# 04_TYPEC.net
KiCad netlist of a schematic drawn in Altium Designer
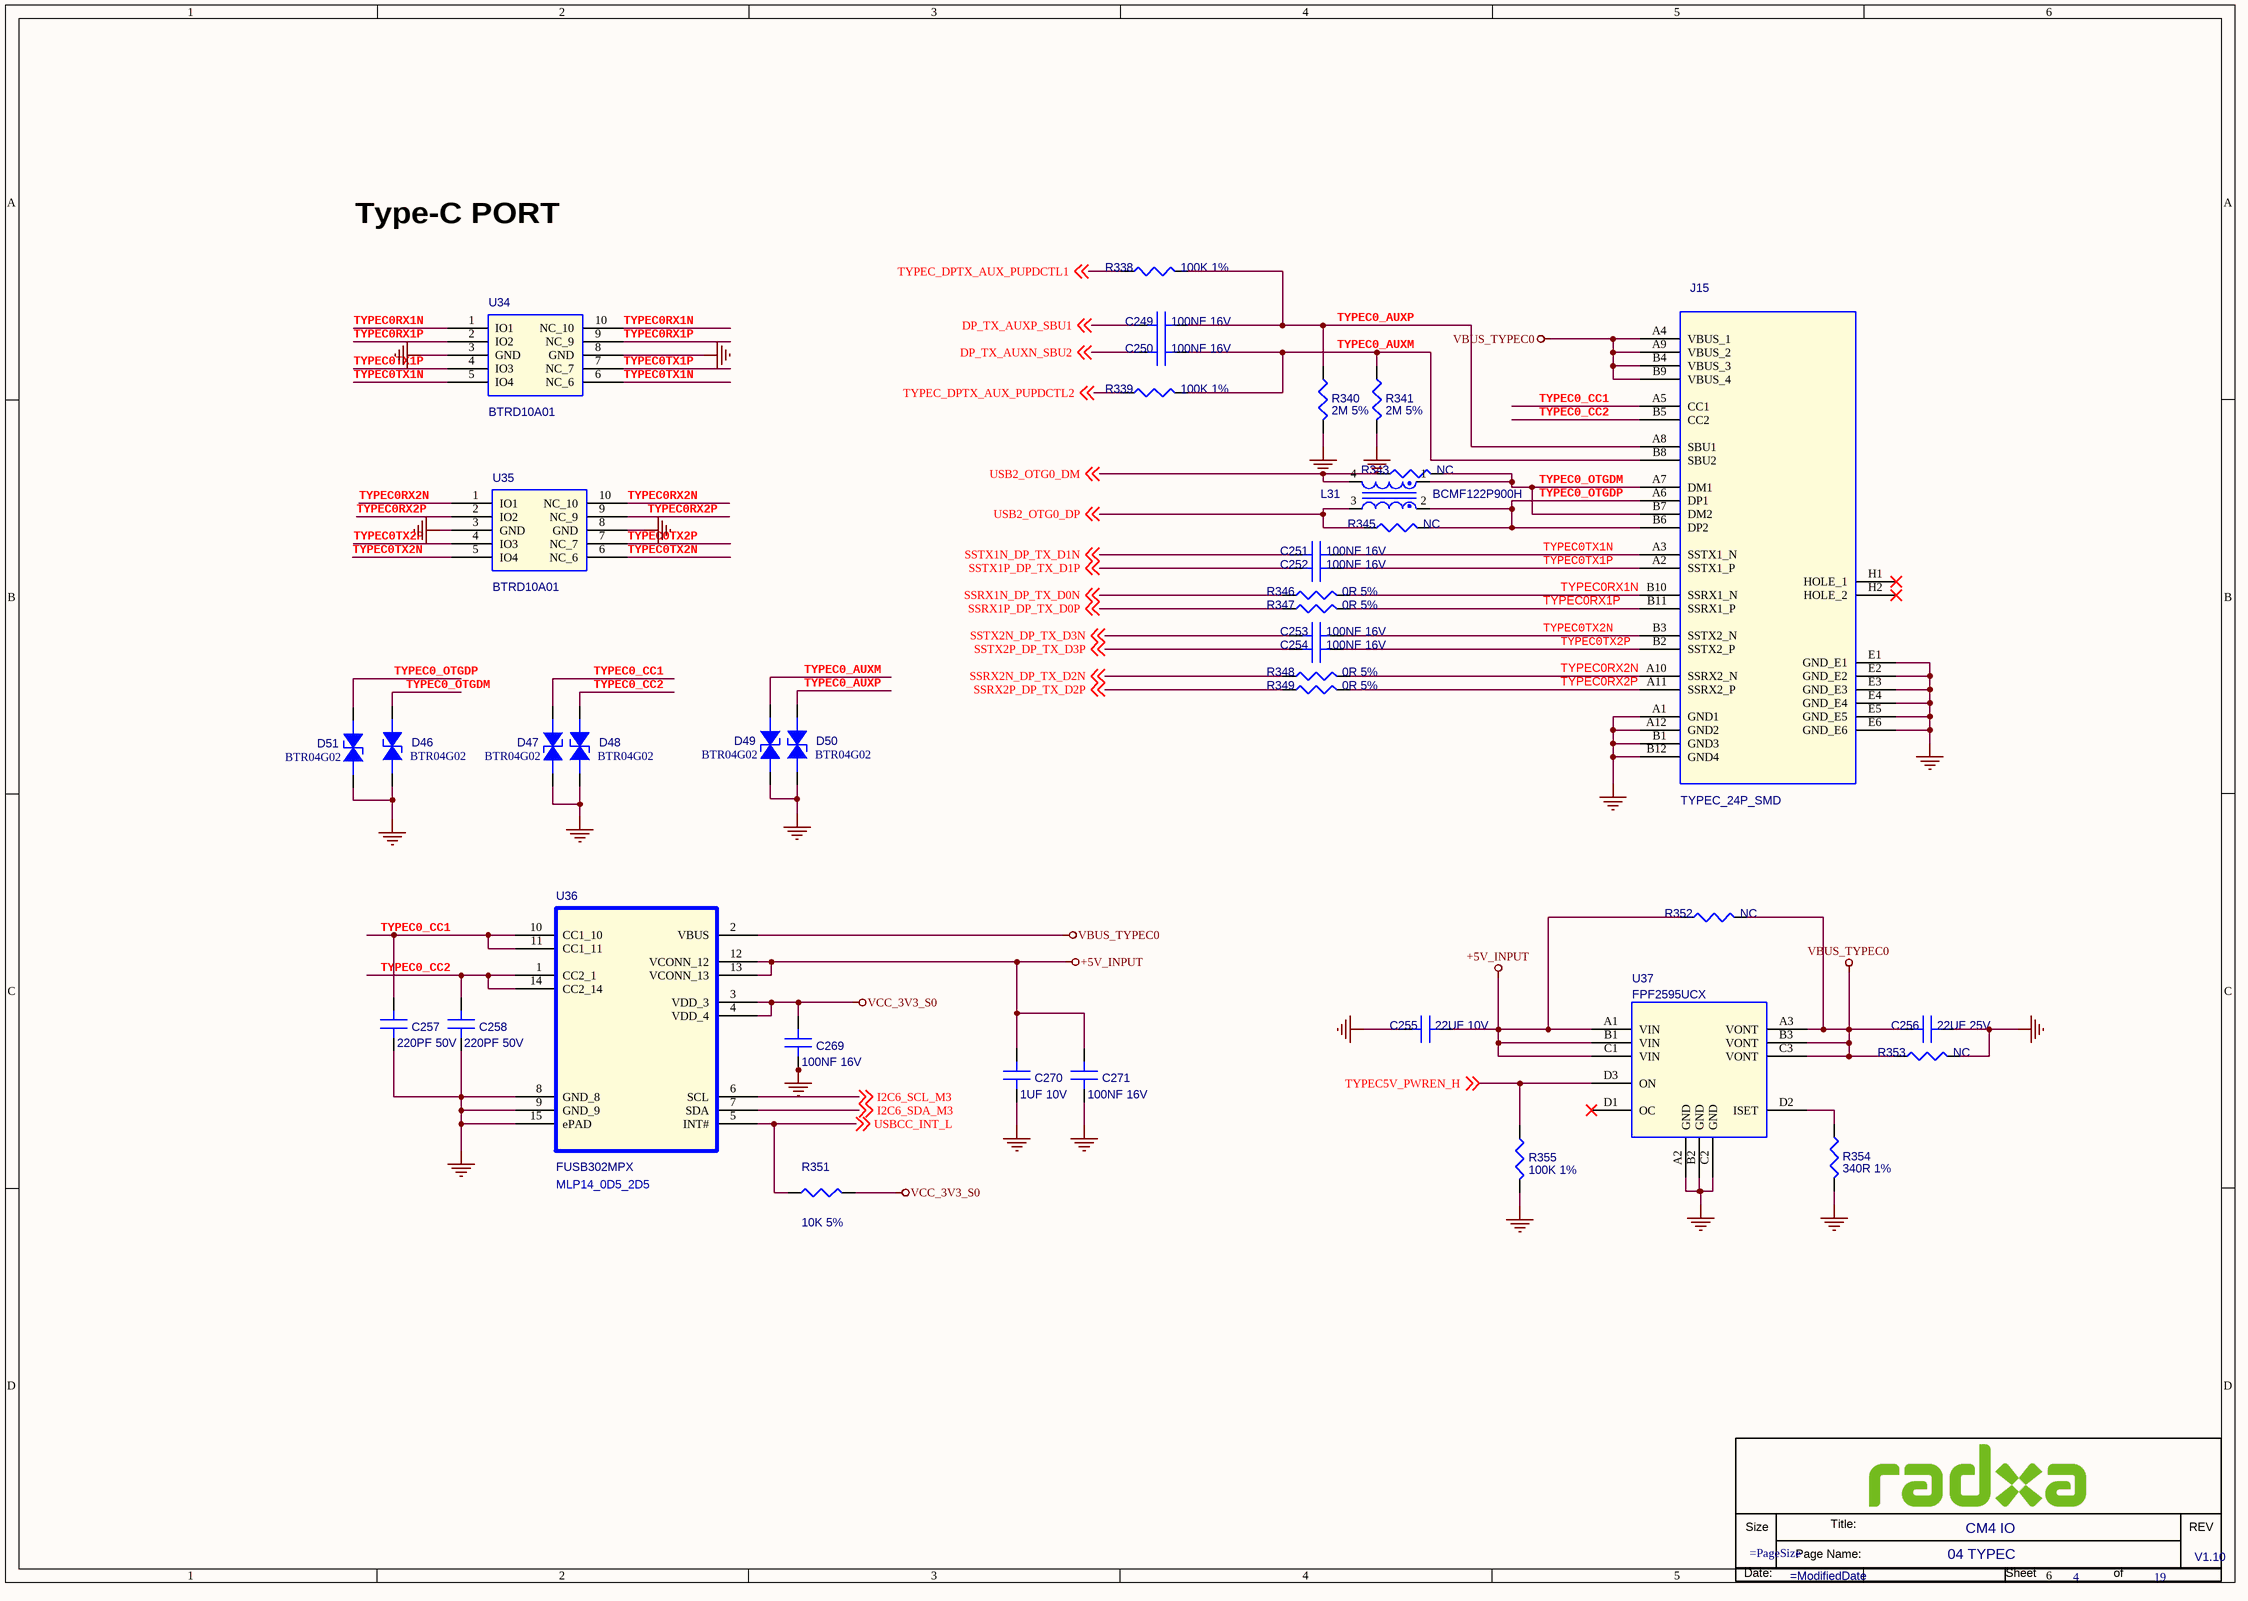
[diagram p0: 04 TYPEC.SchDoc]

(export (version "E")
  (design (tool "Eeschema 10.0.6"))
  (components
    (comp (ref "C249")
      (value "100NF 16V")
      (footprint "C0201")
      (description "SMD  0201  100NF  16V  X5R  ±20%  ROHS")
      (fields (field (name "PART NUMBER") "A1C01.00099"))
      (libsource (lib "*") (part "C"))
    )
    (comp (ref "C250")
      (value "100NF 16V")
      (footprint "C0201")
      (description "SMD  0201  100NF  16V  X5R  ±20%  ROHS")
      (fields (field (name "PART NUMBER") "A1C01.00099"))
      (libsource (lib "*") (part "C"))
    )
    (comp (ref "C251")
      (value "100NF 16V")
      (footprint "C0201")
      (description "SMD  0201  100NF  16V  X5R  ±20%  ROHS")
      (fields (field (name "PART NUMBER") "A1C01.00099"))
      (libsource (lib "*") (part "C"))
    )
    (comp (ref "C252")
      (value "100NF 16V")
      (footprint "C0201")
      (description "SMD  0201  100NF  16V  X5R  ±20%  ROHS")
      (fields (field (name "PART NUMBER") "A1C01.00099"))
      (libsource (lib "*") (part "C"))
    )
    (comp (ref "C253")
      (value "100NF 16V")
      (footprint "C0201")
      (description "SMD  0201  100NF  16V  X5R  ±20%  ROHS")
      (fields (field (name "PART NUMBER") "A1C01.00099"))
      (libsource (lib "*") (part "C"))
    )
    (comp (ref "C254")
      (value "100NF 16V")
      (footprint "C0201")
      (description "SMD  0201  100NF  16V  X5R  ±20%  ROHS")
      (fields (field (name "PART NUMBER") "A1C01.00099"))
      (libsource (lib "*") (part "C"))
    )
    (comp (ref "C255")
      (value "22UF 10V")
      (footprint "C0603")
      (description "SMD  0603  22UF  10V  X5R  ±20%  ROHS")
      (fields (field (name "PART NUMBER") "A1C01.00015"))
      (libsource (lib "*") (part "C"))
    )
    (comp (ref "C256")
      (value "22UF 25V")
      (footprint "C0805")
      (description "SMD  0805  22UF  25V  X5R  ±20%  ROHS")
      (fields (field (name "PART NUMBER") "A1C01.00249"))
      (libsource (lib "*") (part "C"))
    )
    (comp (ref "C257")
      (value "220PF 50V")
      (footprint "C0201")
      (description "SMD  0201  220PF  50V  NPO  ±5%  ROHS")
      (fields (field (name "PART NUMBER") "A1C01.00383"))
      (libsource (lib "*") (part "C"))
    )
    (comp (ref "C258")
      (value "220PF 50V")
      (footprint "C0201")
      (description "SMD  0201  220PF  50V  NPO  ±5%  ROHS")
      (fields (field (name "PART NUMBER") "A1C01.00383"))
      (libsource (lib "*") (part "C"))
    )
    (comp (ref "C269")
      (value "100NF 16V")
      (footprint "C0201")
      (description "SMD  0201  100NF  16V  X5R  ±20%  ROHS")
      (fields (field (name "PART NUMBER") "A1C01.00099"))
      (libsource (lib "*") (part "C"))
    )
    (comp (ref "C270")
      (value "1UF 10V")
      (footprint "C0201")
      (description "SMD  0201  1UF  10V  X5R  ±20%  ROHS")
      (fields (field (name "PART NUMBER") "A1C01.00081"))
      (libsource (lib "*") (part "C"))
    )
    (comp (ref "C271")
      (value "100NF 16V")
      (footprint "C0201")
      (description "SMD  0201  100NF  16V  X5R  ±20%  ROHS")
      (fields (field (name "PART NUMBER") "A1C01.00099"))
      (libsource (lib "*") (part "C"))
    )
    (comp (ref "D46")
      (value "BTR04G02")
      (footprint "DFN1006-2L")
      (description "SMD  编带  0402  BTR04G02  B-tron  ROHS")
      (fields (field (name "PART NUMBER") "A1D02.00002"))
      (libsource (lib "*") (part "ESD"))
    )
    (comp (ref "D47")
      (value "BTR04G02")
      (footprint "DFN1006-2L")
      (description "SMD  编带  0402  BTR04G02  B-tron  ROHS")
      (fields (field (name "PART NUMBER") "A1D02.00002"))
      (libsource (lib "*") (part "ESD"))
    )
    (comp (ref "D48")
      (value "BTR04G02")
      (footprint "DFN1006-2L")
      (description "SMD  编带  0402  BTR04G02  B-tron  ROHS")
      (fields (field (name "PART NUMBER") "A1D02.00002"))
      (libsource (lib "*") (part "ESD"))
    )
    (comp (ref "D49")
      (value "BTR04G02")
      (footprint "DFN1006-2L")
      (description "SMD  编带  0402  BTR04G02  B-tron  ROHS")
      (fields (field (name "PART NUMBER") "A1D02.00002"))
      (libsource (lib "*") (part "ESD"))
    )
    (comp (ref "D50")
      (value "BTR04G02")
      (footprint "DFN1006-2L")
      (description "SMD  编带  0402  BTR04G02  B-tron  ROHS")
      (fields (field (name "PART NUMBER") "A1D02.00002"))
      (libsource (lib "*") (part "ESD"))
    )
    (comp (ref "D51")
      (value "BTR04G02")
      (footprint "DFN1006-2L")
      (description "SMD  编带  0402  BTR04G02  B-tron  ROHS")
      (fields (field (name "PART NUMBER") "A1D02.00002"))
      (libsource (lib "*") (part "ESD"))
    )
    (comp (ref "J15")
      (value "TYPEC_24P_SMD")
      (footprint "TYPEC_SM24P_0D5")
      (description "SMD  母座  2*12PIN  双排  8.94x7.9xH3.2mm  带定位柱  不锈钢  兴联  BUSF242B3N11677  ROHS")
      (fields (field (name "PART NUMBER") "A1J04.00021"))
      (libsource (lib "*") (part "TYPEC_24P_SMD_2"))
    )
    (comp (ref "L31")
      (value "BCMF122P900H")
      (footprint "LC1210")
      (description "SMD  BCMF122P900H  90R  4PIN  不带ESD  ±5%  B-tron  ROHS")
      (fields (field (name "PART NUMBER") "A1L03.00003"))
      (libsource (lib "*") (part "MCZ1210AH900L2"))
    )
    (comp (ref "R338")
      (value "100K 1%")
      (footprint "R0402")
      (description "SMD  0201  100K  1/20W  ±1%  ROHS")
      (fields (field (name "PART NUMBER") "A1R01.00165"))
      (libsource (lib "*") (part "R"))
    )
    (comp (ref "R339")
      (value "100K 1%")
      (footprint "R0402")
      (description "SMD  0201  100K  1/20W  ±1%  ROHS")
      (fields (field (name "PART NUMBER") "A1R01.00165"))
      (libsource (lib "*") (part "R"))
    )
    (comp (ref "R340")
      (value "2M 5%")
      (footprint "R0402")
      (description "SMD  0201  2M  1/20W  ±5%  ROHS")
      (fields (field (name "PART NUMBER") "A1R01.00114"))
      (libsource (lib "*") (part "R"))
    )
    (comp (ref "R341")
      (value "2M 5%")
      (footprint "R0402")
      (description "SMD  0201  2M  1/20W  ±5%  ROHS")
      (fields (field (name "PART NUMBER") "A1R01.00114"))
      (libsource (lib "*") (part "R"))
    )
    (comp (ref "R343")
      (value "NC")
      (footprint "R0402")
      (description "SMD  0201  0R  1/20W  ±5%  ROHS")
      (fields (field (name "PART NUMBER") "A1R01.00027"))
      (libsource (lib "*") (part "R"))
    )
    (comp (ref "R345")
      (value "NC")
      (footprint "R0402")
      (description "SMD  0201  0R  1/20W  ±5%  ROHS")
      (fields (field (name "PART NUMBER") "A1R01.00027"))
      (libsource (lib "*") (part "R"))
    )
    (comp (ref "R346")
      (value "0R 5%")
      (footprint "R0402")
      (description "SMD  0201  0R  1/20W  ±5%  ROHS")
      (fields (field (name "PART NUMBER") "A1R01.00027"))
      (libsource (lib "*") (part "R"))
    )
    (comp (ref "R347")
      (value "0R 5%")
      (footprint "R0402")
      (description "SMD  0201  0R  1/20W  ±5%  ROHS")
      (fields (field (name "PART NUMBER") "A1R01.00027"))
      (libsource (lib "*") (part "R"))
    )
    (comp (ref "R348")
      (value "0R 5%")
      (footprint "R0402")
      (description "SMD  0201  0R  1/20W  ±5%  ROHS")
      (fields (field (name "PART NUMBER") "A1R01.00027"))
      (libsource (lib "*") (part "R"))
    )
    (comp (ref "R349")
      (value "0R 5%")
      (footprint "R0402")
      (description "SMD  0201  0R  1/20W  ±5%  ROHS")
      (fields (field (name "PART NUMBER") "A1R01.00027"))
      (libsource (lib "*") (part "R"))
    )
    (comp (ref "R351")
      (value "10K 5%")
      (footprint "R0402")
      (description "SMD  0201  10K  1/20W  ±5%  ROHS")
      (fields (field (name "PART NUMBER") "A1R01.00012"))
      (libsource (lib "*") (part "R"))
    )
    (comp (ref "R352")
      (value "NC")
      (footprint "R0402")
      (description "SMD  0402  0R  1/16W  ±5%  ROHS")
      (fields (field (name "PART NUMBER") "A1R01.00030"))
      (libsource (lib "*") (part "R"))
    )
    (comp (ref "R353")
      (value "NC")
      (footprint "R0402")
      (description "SMD  0201  4.7K  1/20W  ±5%  ROHS")
      (fields (field (name "PART NUMBER") "A1R01.00014"))
      (libsource (lib "*") (part "R"))
    )
    (comp (ref "R354")
      (value "340R 1%")
      (footprint "R0402")
      (description "SMD  0201  340R  1/20W  ±1%  ROHS")
      (fields (field (name "PART NUMBER") "A1R01.00512"))
      (libsource (lib "*") (part "R"))
    )
    (comp (ref "R355")
      (value "100K 1%")
      (footprint "R0402")
      (description "SMD  0201  100K  1/20W  ±1%  ROHS")
      (fields (field (name "PART NUMBER") "A1R01.00165"))
      (libsource (lib "*") (part "R"))
    )
    (comp (ref "U34")
      (value "BTRD10A01")
      (footprint "SON10_0D5_1")
      (description "SMD  编带  DFN2510-10L  BTRD10A01  4Line  0.1pF  B-tron  ROHS")
      (fields (field (name "PART NUMBER") "A1D02.00106"))
      (libsource (lib "*") (part "BTRD10A01"))
    )
    (comp (ref "U35")
      (value "BTRD10A01")
      (footprint "SON10_0D5_1")
      (description "SMD  编带  DFN2510-10L  BTRD10A01  4Line  0.1pF  B-tron  ROHS")
      (fields (field (name "PART NUMBER") "A1D02.00106"))
      (libsource (lib "*") (part "BTRD10A01"))
    )
    (comp (ref "U36")
      (value "FUSB302MPX")
      (footprint "MLP14_0D5_2D5")
      (description "SMD  USB转换芯片  FUSB302MPX  MLP14  onsemi(安森美)  ROHS")
      (fields (field (name "PCB FOOTPRINT") "MLP14_0D5_2D5") (field (name "PART NUMBER") "A1I01.00760"))
      (libsource (lib "*") (part "FUSB302MPX"))
    )
    (comp (ref "U37")
      (value "FPF2595UCX")
      (footprint "WLCSP12_0D4_1D5")
      (description "SMD  功率电子开关  FPF2595UCX  WLCSP12  ON(安森美)  ROHS")
      (fields (field (name "PART NUMBER") "A1I01.00675"))
      (libsource (lib "*") (part "FPF2595UCX"))
    )
  )
  (nets
    (net (code "1") (name "+5V_INPUT") (class "Default")
      (node (ref "C255") (pin "1") (pinfunction "A_1") (pintype "passive"))
      (node (ref "C270") (pin "1") (pinfunction "A_1") (pintype "passive"))
      (node (ref "C271") (pin "1") (pinfunction "A_1") (pintype "passive"))
      (node (ref "R352") (pin "1") (pinfunction "1_1") (pintype "passive"))
      (node (ref "U36") (pin "12") (pinfunction "VCONN_12_12") (pintype "passive"))
      (node (ref "U36") (pin "13") (pinfunction "VCONN_13_13") (pintype "passive"))
      (node (ref "U37") (pin "A1") (pinfunction "VIN_A1") (pintype "power_in"))
      (node (ref "U37") (pin "B1") (pinfunction "VIN_B1") (pintype "power_in"))
      (node (ref "U37") (pin "C1") (pinfunction "VIN_C1") (pintype "power_in"))
    )
    (net (code "2") (name "/TYPEC0RX1N") (class "Default")
      (node (ref "J15") (pin "B10") (pinfunction "SSRX1_N_B10") (pintype "passive"))
      (node (ref "R346") (pin "2") (pinfunction "2_2") (pintype "passive"))
      (node (ref "U34") (pin "1") (pinfunction "IO1_1") (pintype "passive"))
      (node (ref "U34") (pin "10") (pinfunction "NC_10_10") (pintype "passive"))
    )
    (net (code "3") (name "/TYPEC0RX1P") (class "Default")
      (node (ref "J15") (pin "B11") (pinfunction "SSRX1_P_B11") (pintype "passive"))
      (node (ref "R347") (pin "2") (pinfunction "2_2") (pintype "passive"))
      (node (ref "U34") (pin "2") (pinfunction "IO2_2") (pintype "passive"))
      (node (ref "U34") (pin "9") (pinfunction "NC_9_9") (pintype "passive"))
    )
    (net (code "4") (name "/TYPEC0RX2N") (class "Default")
      (node (ref "J15") (pin "A10") (pinfunction "SSRX2_N_A10") (pintype "passive"))
      (node (ref "R348") (pin "2") (pinfunction "2_2") (pintype "passive"))
      (node (ref "U35") (pin "1") (pinfunction "IO1_1") (pintype "passive"))
      (node (ref "U35") (pin "10") (pinfunction "NC_10_10") (pintype "passive"))
    )
    (net (code "5") (name "/TYPEC0RX2P") (class "Default")
      (node (ref "J15") (pin "A11") (pinfunction "SSRX2_P_A11") (pintype "passive"))
      (node (ref "R349") (pin "2") (pinfunction "2_2") (pintype "passive"))
      (node (ref "U35") (pin "2") (pinfunction "IO2_2") (pintype "passive"))
      (node (ref "U35") (pin "9") (pinfunction "NC_9_9") (pintype "passive"))
    )
    (net (code "6") (name "/TYPEC0TX1N") (class "Default")
      (node (ref "C251") (pin "2") (pinfunction "B_2") (pintype "passive"))
      (node (ref "J15") (pin "A3") (pinfunction "SSTX1_N_A3") (pintype "passive"))
      (node (ref "U34") (pin "5") (pinfunction "IO4_5") (pintype "passive"))
      (node (ref "U34") (pin "6") (pinfunction "NC_6_6") (pintype "passive"))
    )
    (net (code "7") (name "/TYPEC0TX1P") (class "Default")
      (node (ref "C252") (pin "2") (pinfunction "B_2") (pintype "passive"))
      (node (ref "J15") (pin "A2") (pinfunction "SSTX1_P_A2") (pintype "passive"))
      (node (ref "U34") (pin "4") (pinfunction "IO3_4") (pintype "passive"))
      (node (ref "U34") (pin "7") (pinfunction "NC_7_7") (pintype "passive"))
    )
    (net (code "8") (name "/TYPEC0TX2N") (class "Default")
      (node (ref "C253") (pin "2") (pinfunction "B_2") (pintype "passive"))
      (node (ref "J15") (pin "B3") (pinfunction "SSTX2_N_B3") (pintype "passive"))
      (node (ref "U35") (pin "5") (pinfunction "IO4_5") (pintype "passive"))
      (node (ref "U35") (pin "6") (pinfunction "NC_6_6") (pintype "passive"))
    )
    (net (code "9") (name "/TYPEC0TX2P") (class "Default")
      (node (ref "C254") (pin "2") (pinfunction "B_2") (pintype "passive"))
      (node (ref "J15") (pin "B2") (pinfunction "SSTX2_P_B2") (pintype "passive"))
      (node (ref "U35") (pin "4") (pinfunction "IO3_4") (pintype "passive"))
      (node (ref "U35") (pin "7") (pinfunction "NC_7_7") (pintype "passive"))
    )
    (net (code "10") (name "/TYPEC0_AUXM") (class "Default")
      (node (ref "C250") (pin "2") (pinfunction "B_2") (pintype "passive"))
      (node (ref "D49") (pin "2") (pinfunction "CATHODE_2") (pintype "passive"))
      (node (ref "J15") (pin "B8") (pinfunction "SBU2_B8") (pintype "passive"))
      (node (ref "R339") (pin "2") (pinfunction "2_2") (pintype "passive"))
      (node (ref "R341") (pin "1") (pinfunction "1_1") (pintype "passive"))
    )
    (net (code "11") (name "/TYPEC0_AUXP") (class "Default")
      (node (ref "C249") (pin "2") (pinfunction "B_2") (pintype "passive"))
      (node (ref "D50") (pin "2") (pinfunction "CATHODE_2") (pintype "passive"))
      (node (ref "J15") (pin "A8") (pinfunction "SBU1_A8") (pintype "passive"))
      (node (ref "R338") (pin "2") (pinfunction "2_2") (pintype "passive"))
      (node (ref "R340") (pin "1") (pinfunction "1_1") (pintype "passive"))
    )
    (net (code "12") (name "/TYPEC0_CC1") (class "Default")
      (node (ref "C257") (pin "1") (pinfunction "A_1") (pintype "passive"))
      (node (ref "D47") (pin "2") (pinfunction "CATHODE_2") (pintype "passive"))
      (node (ref "J15") (pin "A5") (pinfunction "CC1_A5") (pintype "passive"))
      (node (ref "U36") (pin "10") (pinfunction "CC1_10_10") (pintype "passive"))
      (node (ref "U36") (pin "11") (pinfunction "CC1_11_11") (pintype "passive"))
    )
    (net (code "13") (name "/TYPEC0_CC2") (class "Default")
      (node (ref "C258") (pin "1") (pinfunction "A_1") (pintype "passive"))
      (node (ref "D48") (pin "2") (pinfunction "CATHODE_2") (pintype "passive"))
      (node (ref "J15") (pin "B5") (pinfunction "CC2_B5") (pintype "passive"))
      (node (ref "U36") (pin "1") (pinfunction "CC2_1_1") (pintype "passive"))
      (node (ref "U36") (pin "14") (pinfunction "CC2_14_14") (pintype "passive"))
    )
    (net (code "14") (name "/TYPEC0_OTGDM") (class "Default")
      (node (ref "D46") (pin "2") (pinfunction "CATHODE_2") (pintype "passive"))
      (node (ref "J15") (pin "A7") (pinfunction "DM1_A7") (pintype "passive"))
      (node (ref "J15") (pin "B7") (pinfunction "DM2_B7") (pintype "passive"))
      (node (ref "L31") (pin "1") (pinfunction "1_1") (pintype "passive"))
      (node (ref "R343") (pin "2") (pinfunction "2_2") (pintype "passive"))
    )
    (net (code "15") (name "/TYPEC0_OTGDP") (class "Default")
      (node (ref "D51") (pin "2") (pinfunction "CATHODE_2") (pintype "passive"))
      (node (ref "J15") (pin "A6") (pinfunction "DP1_A6") (pintype "passive"))
      (node (ref "J15") (pin "B6") (pinfunction "DP2_B6") (pintype "passive"))
      (node (ref "L31") (pin "2") (pinfunction "2_2") (pintype "passive"))
      (node (ref "R345") (pin "2") (pinfunction "2_2") (pintype "passive"))
    )
    (net (code "16") (name "DP_TX_AUXN_SBU2") (class "Default")
      (node (ref "C250") (pin "1") (pinfunction "A_1") (pintype "passive"))
    )
    (net (code "17") (name "DP_TX_AUXP_SBU1") (class "Default")
      (node (ref "C249") (pin "1") (pinfunction "A_1") (pintype "passive"))
    )
    (net (code "18") (name "GND") (class "Default")
      (node (ref "C255") (pin "2") (pinfunction "B_2") (pintype "passive"))
      (node (ref "C256") (pin "2") (pinfunction "B_2") (pintype "passive"))
      (node (ref "C257") (pin "2") (pinfunction "B_2") (pintype "passive"))
      (node (ref "C258") (pin "2") (pinfunction "B_2") (pintype "passive"))
      (node (ref "C269") (pin "2") (pinfunction "B_2") (pintype "passive"))
      (node (ref "C270") (pin "2") (pinfunction "B_2") (pintype "passive"))
      (node (ref "C271") (pin "2") (pinfunction "B_2") (pintype "passive"))
      (node (ref "D46") (pin "1") (pinfunction "ANODE_1") (pintype "passive"))
      (node (ref "D47") (pin "1") (pinfunction "ANODE_1") (pintype "passive"))
      (node (ref "D48") (pin "1") (pinfunction "ANODE_1") (pintype "passive"))
      (node (ref "D49") (pin "1") (pinfunction "ANODE_1") (pintype "passive"))
      (node (ref "D50") (pin "1") (pinfunction "ANODE_1") (pintype "passive"))
      (node (ref "D51") (pin "1") (pinfunction "ANODE_1") (pintype "passive"))
      (node (ref "J15") (pin "A1") (pinfunction "GND1_A1") (pintype "passive"))
      (node (ref "J15") (pin "A12") (pinfunction "GND2_A12") (pintype "passive"))
      (node (ref "J15") (pin "B1") (pinfunction "GND3_B1") (pintype "passive"))
      (node (ref "J15") (pin "B12") (pinfunction "GND4_B12") (pintype "passive"))
      (node (ref "J15") (pin "E1") (pinfunction "GND_E1_E1") (pintype "passive"))
      (node (ref "J15") (pin "E2") (pinfunction "GND_E2_E2") (pintype "passive"))
      (node (ref "J15") (pin "E3") (pinfunction "GND_E3_E3") (pintype "passive"))
      (node (ref "J15") (pin "E4") (pinfunction "GND_E4_E4") (pintype "passive"))
      (node (ref "J15") (pin "E5") (pinfunction "GND_E5_E5") (pintype "passive"))
      (node (ref "J15") (pin "E6") (pinfunction "GND_E6_E6") (pintype "passive"))
      (node (ref "R340") (pin "2") (pinfunction "2_2") (pintype "passive"))
      (node (ref "R341") (pin "2") (pinfunction "2_2") (pintype "passive"))
      (node (ref "R353") (pin "2") (pinfunction "2_2") (pintype "passive"))
      (node (ref "R354") (pin "2") (pinfunction "2_2") (pintype "passive"))
      (node (ref "R355") (pin "2") (pinfunction "2_2") (pintype "passive"))
      (node (ref "U34") (pin "3") (pinfunction "GND_3") (pintype "power_in"))
      (node (ref "U34") (pin "8") (pinfunction "GND_8") (pintype "power_in"))
      (node (ref "U35") (pin "3") (pinfunction "GND_3") (pintype "power_in"))
      (node (ref "U35") (pin "8") (pinfunction "GND_8") (pintype "power_in"))
      (node (ref "U36") (pin "15") (pinfunction "ePAD_15") (pintype "power_in"))
      (node (ref "U36") (pin "8") (pinfunction "GND_8_8") (pintype "power_in"))
      (node (ref "U36") (pin "9") (pinfunction "GND_9_9") (pintype "power_in"))
      (node (ref "U37") (pin "A2") (pinfunction "GND_A2") (pintype "power_in"))
      (node (ref "U37") (pin "B2") (pinfunction "GND_B2") (pintype "power_in"))
      (node (ref "U37") (pin "C2") (pinfunction "GND_C2") (pintype "power_in"))
    )
    (net (code "19") (name "I2C6_SCL_M3") (class "Default")
      (node (ref "U36") (pin "6") (pinfunction "SCL_6") (pintype "passive"))
    )
    (net (code "20") (name "I2C6_SDA_M3") (class "Default")
      (node (ref "U36") (pin "7") (pinfunction "SDA_7") (pintype "passive"))
    )
    (net (code "21") (name "Net-(U37-ISET)") (class "Default")
      (node (ref "R354") (pin "1") (pinfunction "1_1") (pintype "passive"))
      (node (ref "U37") (pin "D2") (pinfunction "ISET_D2") (pintype "passive"))
    )
    (net (code "22") (name "SSRX1N_DP_TX_D0N") (class "Default")
      (node (ref "R346") (pin "1") (pinfunction "1_1") (pintype "passive"))
    )
    (net (code "23") (name "SSRX1P_DP_TX_D0P") (class "Default")
      (node (ref "R347") (pin "1") (pinfunction "1_1") (pintype "passive"))
    )
    (net (code "24") (name "SSRX2N_DP_TX_D2N") (class "Default")
      (node (ref "R348") (pin "1") (pinfunction "1_1") (pintype "passive"))
    )
    (net (code "25") (name "SSRX2P_DP_TX_D2P") (class "Default")
      (node (ref "R349") (pin "1") (pinfunction "1_1") (pintype "passive"))
    )
    (net (code "26") (name "SSTX1N_DP_TX_D1N") (class "Default")
      (node (ref "C251") (pin "1") (pinfunction "A_1") (pintype "passive"))
    )
    (net (code "27") (name "SSTX1P_DP_TX_D1P") (class "Default")
      (node (ref "C252") (pin "1") (pinfunction "A_1") (pintype "passive"))
    )
    (net (code "28") (name "SSTX2N_DP_TX_D3N") (class "Default")
      (node (ref "C253") (pin "1") (pinfunction "A_1") (pintype "passive"))
    )
    (net (code "29") (name "SSTX2P_DP_TX_D3P") (class "Default")
      (node (ref "C254") (pin "1") (pinfunction "A_1") (pintype "passive"))
    )
    (net (code "30") (name "TYPEC5V_PWREN_H") (class "Default")
      (node (ref "R355") (pin "1") (pinfunction "1_1") (pintype "passive"))
      (node (ref "U37") (pin "D3") (pinfunction "ON_D3") (pintype "passive"))
    )
    (net (code "31") (name "TYPEC_DPTX_AUX_PUPDCTL1") (class "Default")
      (node (ref "R338") (pin "1") (pinfunction "1_1") (pintype "passive"))
    )
    (net (code "32") (name "TYPEC_DPTX_AUX_PUPDCTL2") (class "Default")
      (node (ref "R339") (pin "1") (pinfunction "1_1") (pintype "passive"))
    )
    (net (code "33") (name "USB2_OTG0_DM") (class "Default")
      (node (ref "L31") (pin "4") (pinfunction "4_4") (pintype "passive"))
      (node (ref "R343") (pin "1") (pinfunction "1_1") (pintype "passive"))
    )
    (net (code "34") (name "USB2_OTG0_DP") (class "Default")
      (node (ref "L31") (pin "3") (pinfunction "3_3") (pintype "passive"))
      (node (ref "R345") (pin "1") (pinfunction "1_1") (pintype "passive"))
    )
    (net (code "35") (name "USBCC_INT_L") (class "Default")
      (node (ref "R351") (pin "2") (pinfunction "2_2") (pintype "passive"))
      (node (ref "U36") (pin "5") (pinfunction "INT#_5") (pintype "passive"))
    )
    (net (code "36") (name "VBUS_TYPEC0") (class "Default")
      (node (ref "C256") (pin "1") (pinfunction "A_1") (pintype "passive"))
      (node (ref "J15") (pin "A4") (pinfunction "VBUS_1_A4") (pintype "passive"))
      (node (ref "J15") (pin "A9") (pinfunction "VBUS_2_A9") (pintype "passive"))
      (node (ref "J15") (pin "B4") (pinfunction "VBUS_3_B4") (pintype "passive"))
      (node (ref "J15") (pin "B9") (pinfunction "VBUS_4_B9") (pintype "passive"))
      (node (ref "R352") (pin "2") (pinfunction "2_2") (pintype "passive"))
      (node (ref "R353") (pin "1") (pinfunction "1_1") (pintype "passive"))
      (node (ref "U36") (pin "2") (pinfunction "VBUS_2") (pintype "passive"))
      (node (ref "U37") (pin "A3") (pinfunction "VONT_A3") (pintype "power_in"))
      (node (ref "U37") (pin "B3") (pinfunction "VONT_B3") (pintype "power_in"))
      (node (ref "U37") (pin "C3") (pinfunction "VONT_C3") (pintype "power_in"))
    )
    (net (code "37") (name "VCC_3V3_S0") (class "Default")
      (node (ref "C269") (pin "1") (pinfunction "A_1") (pintype "passive"))
      (node (ref "R351") (pin "1") (pinfunction "1_1") (pintype "passive"))
      (node (ref "U36") (pin "3") (pinfunction "VDD_3_3") (pintype "power_in"))
      (node (ref "U36") (pin "4") (pinfunction "VDD_4_4") (pintype "power_in"))
    )
    (net (code "38") (name "unconnected-(J15-HOLE_1-PadH1)") (class "Default")
      (node (ref "J15") (pin "H1") (pinfunction "HOLE_1_H1") (pintype "passive+no_connect"))
    )
    (net (code "39") (name "unconnected-(J15-HOLE_2-PadH2)") (class "Default")
      (node (ref "J15") (pin "H2") (pinfunction "HOLE_2_H2") (pintype "passive+no_connect"))
    )
    (net (code "40") (name "unconnected-(U37-OC-PadD1)") (class "Default")
      (node (ref "U37") (pin "D1") (pinfunction "OC_D1") (pintype "passive+no_connect"))
    )
  )
)
